# Guindeau_control.net
KiCad netlist of a schematic drawn in EasyEDA
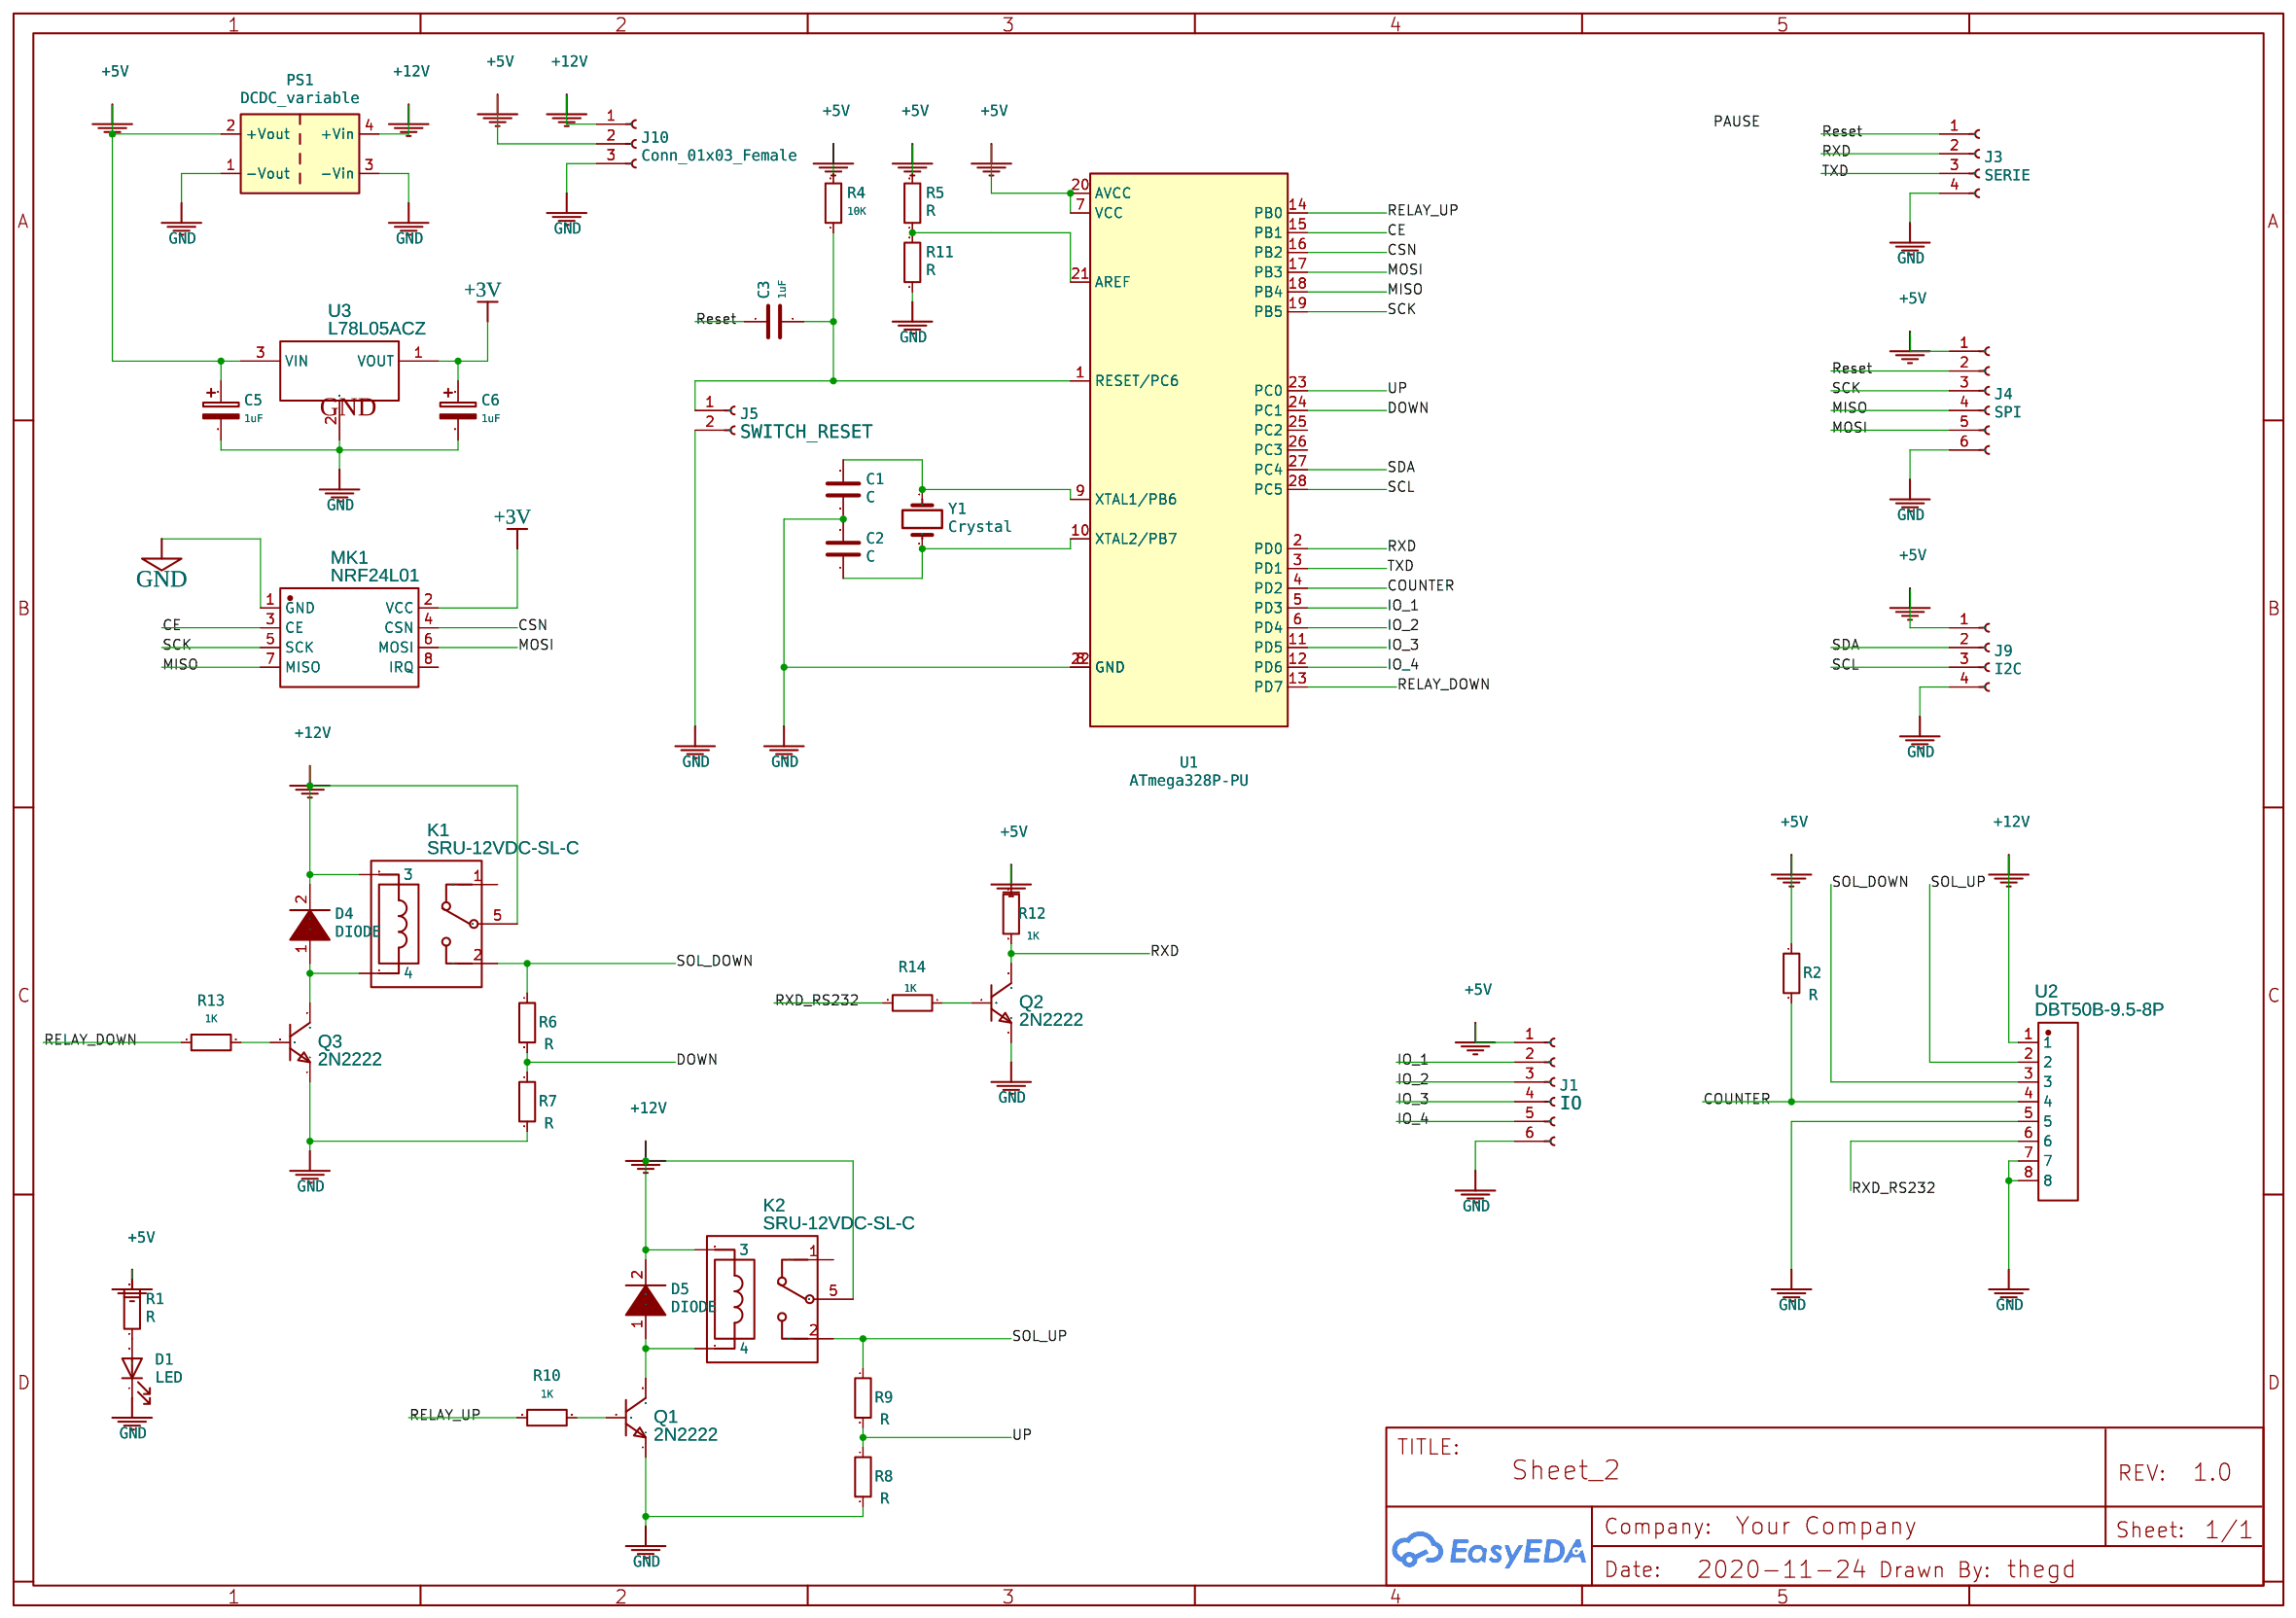
[diagram p0: schematic sheet]

(export (version "E")
  (design (tool "Eeschema 10.0.6"))
  (components
    (comp (ref "C1") (value "C") (libsource (lib "") (part "Unknown_420_-565")))
    (comp (ref "C2") (value "C") (libsource (lib "") (part "Unknown_420_-535")))
    (comp (ref "C3") (value "1uF") (libsource (lib "") (part "Unknown_385_-650")))
    (comp (ref "C5") (value "1uF") (libsource (lib "") (part "Unknown_105_-605")))
    (comp (ref "C6") (value "1uF") (libsource (lib "") (part "Unknown_225_-605")))
    (comp (ref "D1") (value "LED") (libsource (lib "") (part "Unknown_60_-120")))
    (comp (ref "D4") (value "DIODE") (libsource (lib "") (part "Unknown_150_-345")))
    (comp (ref "D5") (value "DIODE") (libsource (lib "") (part "Unknown_320_-155")))
    (comp (ref "J1") (value "IO") (libsource (lib "") (part "Unknown_780_-265")))
    (comp (ref "J3") (value "SERIE") (libsource (lib "") (part "Unknown_995_-735")))
    (comp (ref "J4") (value "SPI") (libsource (lib "") (part "Unknown_1000_-615")))
    (comp (ref "J5") (value "SWITCH_RESET") (libsource (lib "") (part "Unknown_365_-605")))
    (comp (ref "J9") (value "I2C") (libsource (lib "") (part "Unknown_1000_-485")))
    (comp (ref "J10") (value "Conn_01x03_Female") (libsource (lib "") (part "Unknown_315_-740")))
    (comp (ref "K1")
      (value "SRU-12VDC-SL-C")
      (fields (field (name "BOM_Supplier Part") "C47402"))
      (libsource (lib "") (part "SRU-12VDC-SL-C"))
    )
    (comp (ref "K2")
      (value "SRU-12VDC-SL-C")
      (fields (field (name "BOM_Supplier Part") "C47402"))
      (libsource (lib "") (part "SRU-12VDC-SL-C"))
    )
    (comp (ref "MK1")
      (value "NRF24L01")
      (fields
        (field (name "BOM_Manufacturer Part") "NRF24L01+功率加强版绑定2.4Gwireless module")
        (field (name "BOM_Supplier Part") "C90751")
      )
      (libsource (lib "") (part "NRF24L01"))
    )
    (comp (ref "PS1") (value "DCDC_variable") (libsource (lib "") (part "Unknown_145_-735")))
    (comp (ref "Q1")
      (value "2N2222")
      (fields (field (name "BOM_Supplier Part") "C118536"))
      (libsource (lib "") (part "2N2222"))
    )
    (comp (ref "Q2")
      (value "2N2222")
      (fields (field (name "BOM_Supplier Part") "C118536"))
      (libsource (lib "") (part "2N2222"))
    )
    (comp (ref "Q3")
      (value "2N2222")
      (fields (field (name "BOM_Supplier Part") "C118536"))
      (libsource (lib "") (part "2N2222"))
    )
    (comp (ref "R1") (value "R") (libsource (lib "") (part "Unknown_60_-150")))
    (comp (ref "R2") (value "R") (libsource (lib "") (part "Unknown_900_-320")))
    (comp (ref "R4") (value "10K") (libsource (lib "") (part "Unknown_415_-710")))
    (comp (ref "R5") (value "R") (libsource (lib "") (part "Unknown_455_-710")))
    (comp (ref "R6") (value "R") (libsource (lib "") (part "Unknown_260_-295")))
    (comp (ref "R7") (value "R") (libsource (lib "") (part "Unknown_260_-255")))
    (comp (ref "R8") (value "R") (libsource (lib "") (part "Unknown_430_-65")))
    (comp (ref "R9") (value "R") (libsource (lib "") (part "Unknown_430_-105")))
    (comp (ref "R10") (value "1K") (libsource (lib "") (part "Unknown_270_-95")))
    (comp (ref "R11") (value "R") (libsource (lib "") (part "Unknown_455_-680")))
    (comp (ref "R12") (value "1K") (libsource (lib "") (part "Unknown_505_-350")))
    (comp (ref "R13") (value "1K") (libsource (lib "") (part "Unknown_100_-285")))
    (comp (ref "R14") (value "1K") (libsource (lib "") (part "Unknown_455_-305")))
    (comp (ref "U1") (value "ATmega328P-PU") (libsource (lib "") (part "Unknown_595_-585")))
    (comp (ref "U2")
      (value "DBT50B-9.5-8P")
      (fields (field (name "BOM_Supplier Part") "C729817"))
      (libsource (lib "") (part "DBT50B-9.5-8P"))
    )
    (comp (ref "U3")
      (value "L78L05ACZ")
      (fields (field (name "BOM_Supplier Part") "C57900"))
      (libsource (lib "") (part "L78L05ACZ"))
    )
    (comp (ref "Y1") (value "Crystal") (libsource (lib "") (part "Unknown_460_-550")))
  )
  (nets
    (net (code "1") (name "+3V") (class "Default")
      (node (ref "C6") (pin "1") (pintype "unspecified"))
      (node (ref "MK1") (pin "2") (pinfunction "VCC_2") (pintype "unspecified"))
      (node (ref "U3") (pin "1") (pinfunction "VOUT_1") (pintype "passive"))
    )
    (net (code "2") (name "+5V") (class "Default")
      (node (ref "C5") (pin "1") (pintype "unspecified"))
      (node (ref "J1") (pin "1") (pinfunction "Pin_1_1") (pintype "unspecified"))
      (node (ref "J10") (pin "2") (pinfunction "Pin_2_2") (pintype "unspecified"))
      (node (ref "J4") (pin "1") (pinfunction "Pin_1_1") (pintype "unspecified"))
      (node (ref "J9") (pin "1") (pinfunction "Pin_1_1") (pintype "unspecified"))
      (node (ref "PS1") (pin "2") (pinfunction "+Vout_2") (pintype "bidirectional"))
      (node (ref "R1") (pin "2") (pintype "unspecified"))
      (node (ref "R12") (pin "1") (pintype "unspecified"))
      (node (ref "R2") (pin "1") (pintype "unspecified"))
      (node (ref "R4") (pin "2") (pintype "unspecified"))
      (node (ref "R5") (pin "2") (pintype "unspecified"))
      (node (ref "U1") (pin "20") (pinfunction "AVCC_20") (pintype "bidirectional"))
      (node (ref "U1") (pin "7") (pinfunction "VCC_7") (pintype "bidirectional"))
      (node (ref "U3") (pin "3") (pinfunction "VIN_3") (pintype "passive"))
    )
    (net (code "3") (name "+12V") (class "Default")
      (node (ref "D4") (pin "2") (pinfunction "A_2") (pintype "input"))
      (node (ref "D5") (pin "2") (pinfunction "A_2") (pintype "input"))
      (node (ref "J10") (pin "1") (pinfunction "Pin_1_1") (pintype "unspecified"))
      (node (ref "K1") (pin "3") (pinfunction "3_3") (pintype "unspecified"))
      (node (ref "K1") (pin "5") (pinfunction "5_5") (pintype "unspecified"))
      (node (ref "K2") (pin "3") (pinfunction "3_3") (pintype "unspecified"))
      (node (ref "K2") (pin "5") (pinfunction "5_5") (pintype "unspecified"))
      (node (ref "PS1") (pin "4") (pinfunction "+Vin_4") (pintype "bidirectional"))
      (node (ref "U2") (pin "1") (pinfunction "1_1") (pintype "unspecified"))
    )
    (net (code "4") (name "/CE") (class "Default")
      (node (ref "MK1") (pin "3") (pinfunction "CE_3") (pintype "unspecified"))
      (node (ref "U1") (pin "15") (pinfunction "PB1_15") (pintype "bidirectional"))
    )
    (net (code "5") (name "/COUNTER") (class "Default")
      (node (ref "R2") (pin "2") (pintype "unspecified"))
      (node (ref "U1") (pin "4") (pinfunction "PD2_4") (pintype "bidirectional"))
      (node (ref "U2") (pin "4") (pinfunction "4_4") (pintype "unspecified"))
    )
    (net (code "6") (name "/CSN") (class "Default")
      (node (ref "MK1") (pin "4") (pinfunction "CSN_4") (pintype "unspecified"))
      (node (ref "U1") (pin "16") (pinfunction "PB2_16") (pintype "bidirectional"))
    )
    (net (code "7") (name "/DOWN") (class "Default")
      (node (ref "R6") (pin "2") (pintype "unspecified"))
      (node (ref "R7") (pin "1") (pintype "unspecified"))
      (node (ref "U1") (pin "24") (pinfunction "PC1_24") (pintype "bidirectional"))
    )
    (net (code "8") (name "/IO_1") (class "Default")
      (node (ref "J1") (pin "2") (pinfunction "Pin_2_2") (pintype "unspecified"))
      (node (ref "U1") (pin "5") (pinfunction "PD3_5") (pintype "bidirectional"))
    )
    (net (code "9") (name "/IO_2") (class "Default")
      (node (ref "J1") (pin "3") (pinfunction "Pin_3_3") (pintype "unspecified"))
      (node (ref "U1") (pin "6") (pinfunction "PD4_6") (pintype "bidirectional"))
    )
    (net (code "10") (name "/IO_3") (class "Default")
      (node (ref "J1") (pin "4") (pinfunction "Pin_4_4") (pintype "unspecified"))
      (node (ref "U1") (pin "11") (pinfunction "PD5_11") (pintype "bidirectional"))
    )
    (net (code "11") (name "/IO_4") (class "Default")
      (node (ref "J1") (pin "5") (pinfunction "Pin_5_5") (pintype "unspecified"))
      (node (ref "U1") (pin "12") (pinfunction "PD6_12") (pintype "bidirectional"))
    )
    (net (code "12") (name "/MISO") (class "Default")
      (node (ref "J4") (pin "4") (pinfunction "Pin_4_4") (pintype "unspecified"))
      (node (ref "MK1") (pin "7") (pinfunction "MISO_7") (pintype "unspecified"))
      (node (ref "U1") (pin "18") (pinfunction "PB4_18") (pintype "bidirectional"))
    )
    (net (code "13") (name "/MOSI") (class "Default")
      (node (ref "J4") (pin "5") (pinfunction "Pin_5_5") (pintype "unspecified"))
      (node (ref "MK1") (pin "6") (pinfunction "MOSI_6") (pintype "unspecified"))
      (node (ref "U1") (pin "17") (pinfunction "PB3_17") (pintype "bidirectional"))
    )
    (net (code "15") (name "/RELAY_DOWN") (class "Default")
      (node (ref "R13") (pin "1") (pintype "unspecified"))
      (node (ref "U1") (pin "13") (pinfunction "PD7_13") (pintype "bidirectional"))
    )
    (net (code "16") (name "/RELAY_UP") (class "Default")
      (node (ref "R10") (pin "1") (pintype "unspecified"))
      (node (ref "U1") (pin "14") (pinfunction "PB0_14") (pintype "bidirectional"))
    )
    (net (code "17") (name "/RXD") (class "Default")
      (node (ref "J3") (pin "2") (pinfunction "Pin_2_2") (pintype "unspecified"))
      (node (ref "Q2") (pin "3") (pinfunction "C_3") (pintype "unspecified"))
      (node (ref "R12") (pin "2") (pintype "unspecified"))
      (node (ref "U1") (pin "2") (pinfunction "PD0_2") (pintype "bidirectional"))
    )
    (net (code "18") (name "/RXD_RS232") (class "Default")
      (node (ref "R14") (pin "2") (pintype "unspecified"))
      (node (ref "U2") (pin "6") (pinfunction "6_6") (pintype "unspecified"))
    )
    (net (code "19") (name "/Reset") (class "Default")
      (node (ref "C3") (pin "1") (pintype "unspecified"))
      (node (ref "J3") (pin "1") (pinfunction "Pin_1_1") (pintype "unspecified"))
      (node (ref "J4") (pin "2") (pinfunction "Pin_2_2") (pintype "unspecified"))
    )
    (net (code "20") (name "/SCK") (class "Default")
      (node (ref "J4") (pin "3") (pinfunction "Pin_3_3") (pintype "unspecified"))
      (node (ref "MK1") (pin "5") (pinfunction "SCK_5") (pintype "unspecified"))
      (node (ref "U1") (pin "19") (pinfunction "PB5_19") (pintype "bidirectional"))
    )
    (net (code "21") (name "/SCL") (class "Default")
      (node (ref "J9") (pin "3") (pinfunction "Pin_3_3") (pintype "unspecified"))
      (node (ref "U1") (pin "28") (pinfunction "PC5_28") (pintype "bidirectional"))
    )
    (net (code "22") (name "/SDA") (class "Default")
      (node (ref "J9") (pin "2") (pinfunction "Pin_2_2") (pintype "unspecified"))
      (node (ref "U1") (pin "27") (pinfunction "PC4_27") (pintype "bidirectional"))
    )
    (net (code "23") (name "/SOL_DOWN") (class "Default")
      (node (ref "K1") (pin "2") (pinfunction "2_2") (pintype "unspecified"))
      (node (ref "R6") (pin "1") (pintype "unspecified"))
      (node (ref "U2") (pin "3") (pinfunction "3_3") (pintype "unspecified"))
    )
    (net (code "24") (name "/SOL_UP") (class "Default")
      (node (ref "K2") (pin "2") (pinfunction "2_2") (pintype "unspecified"))
      (node (ref "R9") (pin "1") (pintype "unspecified"))
      (node (ref "U2") (pin "2") (pinfunction "2_2") (pintype "unspecified"))
    )
    (net (code "25") (name "/TXD") (class "Default")
      (node (ref "J3") (pin "3") (pinfunction "Pin_3_3") (pintype "unspecified"))
      (node (ref "U1") (pin "3") (pinfunction "PD1_3") (pintype "bidirectional"))
    )
    (net (code "26") (name "/UP") (class "Default")
      (node (ref "R8") (pin "1") (pintype "unspecified"))
      (node (ref "R9") (pin "2") (pintype "unspecified"))
      (node (ref "U1") (pin "23") (pinfunction "PC0_23") (pintype "bidirectional"))
    )
    (net (code "27") (name "GND") (class "Default")
      (node (ref "C1") (pin "2") (pintype "unspecified"))
      (node (ref "C2") (pin "1") (pintype "unspecified"))
      (node (ref "C5") (pin "2") (pintype "unspecified"))
      (node (ref "C6") (pin "2") (pintype "unspecified"))
      (node (ref "D1") (pin "1") (pinfunction "K_1") (pintype "unspecified"))
      (node (ref "J1") (pin "6") (pinfunction "Pin_6_6") (pintype "unspecified"))
      (node (ref "J10") (pin "3") (pinfunction "Pin_3_3") (pintype "unspecified"))
      (node (ref "J3") (pin "4") (pinfunction "Pin_4_4") (pintype "unspecified"))
      (node (ref "J4") (pin "6") (pinfunction "Pin_6_6") (pintype "unspecified"))
      (node (ref "J5") (pin "2") (pinfunction "Pin_2_2") (pintype "unspecified"))
      (node (ref "J9") (pin "4") (pinfunction "Pin_4_4") (pintype "unspecified"))
      (node (ref "MK1") (pin "1") (pinfunction "GND_1") (pintype "unspecified"))
      (node (ref "PS1") (pin "1") (pinfunction "-Vout_1") (pintype "bidirectional"))
      (node (ref "PS1") (pin "3") (pinfunction "-Vin_3") (pintype "bidirectional"))
      (node (ref "Q1") (pin "1") (pinfunction "E_1") (pintype "unspecified"))
      (node (ref "Q2") (pin "1") (pinfunction "E_1") (pintype "unspecified"))
      (node (ref "Q3") (pin "1") (pinfunction "E_1") (pintype "unspecified"))
      (node (ref "R11") (pin "1") (pintype "unspecified"))
      (node (ref "R7") (pin "2") (pintype "unspecified"))
      (node (ref "R8") (pin "2") (pintype "unspecified"))
      (node (ref "U1") (pin "22") (pinfunction "GND_22") (pintype "unspecified"))
      (node (ref "U1") (pin "8") (pinfunction "GND_8") (pintype "bidirectional"))
      (node (ref "U2") (pin "5") (pinfunction "5_5") (pintype "unspecified"))
      (node (ref "U2") (pin "7") (pinfunction "7_7") (pintype "unspecified"))
      (node (ref "U2") (pin "8") (pinfunction "8_8") (pintype "unspecified"))
      (node (ref "U3") (pin "2") (pinfunction "GND_2") (pintype "passive"))
    )
    (net (code "28") (name "Net-(D1-A)") (class "Default")
      (node (ref "D1") (pin "2") (pinfunction "A_2") (pintype "unspecified"))
      (node (ref "R1") (pin "1") (pintype "unspecified"))
    )
    (net (code "29") (name "Net-(D4-K)") (class "Default")
      (node (ref "D4") (pin "1") (pinfunction "K_1") (pintype "input"))
      (node (ref "K1") (pin "4") (pinfunction "4_4") (pintype "unspecified"))
      (node (ref "Q3") (pin "3") (pinfunction "C_3") (pintype "unspecified"))
    )
    (net (code "30") (name "Net-(D5-K)") (class "Default")
      (node (ref "D5") (pin "1") (pinfunction "K_1") (pintype "input"))
      (node (ref "K2") (pin "4") (pinfunction "4_4") (pintype "unspecified"))
      (node (ref "Q1") (pin "3") (pinfunction "C_3") (pintype "unspecified"))
    )
    (net (code "31") (name "Net-(J5-Pin_1)") (class "Default")
      (node (ref "C3") (pin "2") (pintype "unspecified"))
      (node (ref "J5") (pin "1") (pinfunction "Pin_1_1") (pintype "unspecified"))
      (node (ref "R4") (pin "1") (pintype "unspecified"))
      (node (ref "U1") (pin "1") (pinfunction "RESET/PC6_1") (pintype "bidirectional"))
    )
    (net (code "32") (name "Net-(Q1-B)") (class "Default")
      (node (ref "Q1") (pin "2") (pinfunction "B_2") (pintype "unspecified"))
      (node (ref "R10") (pin "2") (pintype "unspecified"))
    )
    (net (code "33") (name "Net-(Q2-B)") (class "Default")
      (node (ref "Q2") (pin "2") (pinfunction "B_2") (pintype "unspecified"))
      (node (ref "R14") (pin "1") (pintype "unspecified"))
    )
    (net (code "34") (name "Net-(Q3-B)") (class "Default")
      (node (ref "Q3") (pin "2") (pinfunction "B_2") (pintype "unspecified"))
      (node (ref "R13") (pin "2") (pintype "unspecified"))
    )
    (net (code "35") (name "Net-(U1-AREF)") (class "Default")
      (node (ref "R11") (pin "2") (pintype "unspecified"))
      (node (ref "R5") (pin "1") (pintype "unspecified"))
      (node (ref "U1") (pin "21") (pinfunction "AREF_21") (pintype "unspecified"))
    )
    (net (code "36") (name "Net-(U1-XTAL1{slash}PB6)") (class "Default")
      (node (ref "C1") (pin "1") (pintype "unspecified"))
      (node (ref "U1") (pin "9") (pinfunction "XTAL1/PB6_9") (pintype "bidirectional"))
      (node (ref "Y1") (pin "1") (pinfunction "1_1") (pintype "unspecified"))
    )
    (net (code "37") (name "Net-(U1-XTAL2{slash}PB7)") (class "Default")
      (node (ref "C2") (pin "2") (pintype "unspecified"))
      (node (ref "U1") (pin "10") (pinfunction "XTAL2/PB7_10") (pintype "bidirectional"))
      (node (ref "Y1") (pin "2") (pinfunction "2_2") (pintype "unspecified"))
    )
    (net (code "38") (name "unconnected-(K1-Pad1)") (class "Default")
      (node (ref "K1") (pin "1") (pinfunction "1_1") (pintype "unspecified"))
    )
    (net (code "39") (name "unconnected-(K2-Pad1)") (class "Default")
      (node (ref "K2") (pin "1") (pinfunction "1_1") (pintype "unspecified"))
    )
    (net (code "40") (name "unconnected-(MK1-IRQ-Pad8)") (class "Default")
      (node (ref "MK1") (pin "8") (pinfunction "IRQ_8") (pintype "unspecified"))
    )
    (net (code "41") (name "unconnected-(U1-PC2-Pad25)") (class "Default")
      (node (ref "U1") (pin "25") (pinfunction "PC2_25") (pintype "bidirectional"))
    )
    (net (code "42") (name "unconnected-(U1-PC3-Pad26)") (class "Default")
      (node (ref "U1") (pin "26") (pinfunction "PC3_26") (pintype "bidirectional"))
    )
  )
)
